# Power.net
KiCad netlist of a schematic drawn in Altium Designer
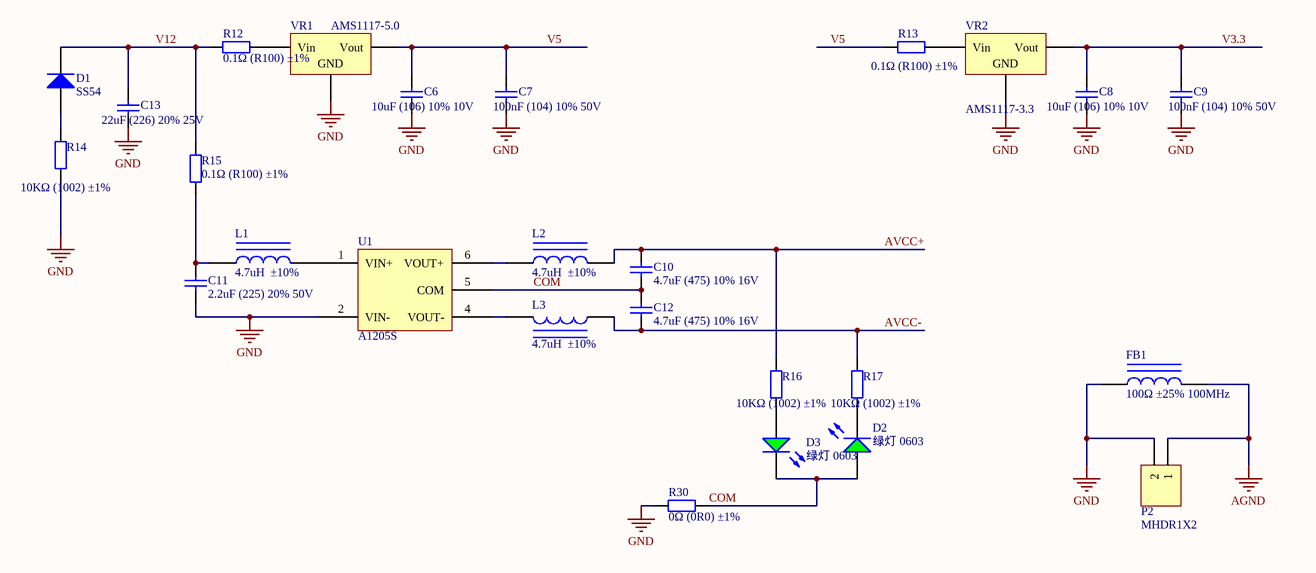
[diagram p0: Power.SchDoc]

(export (version "E")
  (design (tool "Eeschema 10.0.6"))
  (components
    (comp (ref "C6")
      (value "10uF (106) 10% 10V")
      (footprint "0603_C")
      (description "贴片电容")
      (libsource (lib "Miscellaneous Devices LC") (part "0603 10uF (106) 10% 10V"))
    )
    (comp (ref "C7")
      (value "100nF (104) 10% 50V")
      (footprint "0603_C")
      (description "贴片电容")
      (libsource (lib "Miscellaneous Devices LC") (part "0603 100nF (104) 10% 50V"))
    )
    (comp (ref "C8")
      (value "10uF (106) 10% 10V")
      (footprint "0603_C")
      (description "贴片电容")
      (libsource (lib "Miscellaneous Devices LC") (part "0603 10uF (106) 10% 10V"))
    )
    (comp (ref "C9")
      (value "100nF (104) 10% 50V")
      (footprint "0603_C")
      (description "贴片电容")
      (libsource (lib "Miscellaneous Devices LC") (part "0603 100nF (104) 10% 50V"))
    )
    (comp (ref "C10")
      (value "4.7uF (475) 10% 16V")
      (footprint "0603_C")
      (description "贴片电容")
      (libsource (lib "Miscellaneous Devices LC") (part "0603 4.7uF (475) 10% 16V"))
    )
    (comp (ref "C11")
      (value "2.2uF (225) 20% 50V")
      (footprint "0805_C")
      (description "贴片电容")
      (libsource (lib "Miscellaneous Devices LC") (part "0805 2.2uF (225) 20% 50V"))
    )
    (comp (ref "C12")
      (value "4.7uF (475) 10% 16V")
      (footprint "0603_C")
      (description "贴片电容")
      (libsource (lib "Miscellaneous Devices LC") (part "0603 4.7uF (475) 10% 16V"))
    )
    (comp (ref "C13")
      (value "22uF (226) 20% 25V")
      (footprint "0805_C")
      (description "贴片电容")
      (libsource (lib "Miscellaneous Devices LC") (part "0805 22uF (226) 20% 25V"))
    )
    (comp (ref "D1")
      (value "SS54")
      (footprint "SMA(DO-214AC)_S1")
      (description "二极管")
      (libsource (lib "Miscellaneous Devices LC") (part "SMA(DO-214AC) SS54"))
    )
    (comp (ref "D2")
      (value "绿灯 0603")
      (footprint "0603_LED_S1")
      (description "发光二极管")
      (libsource (lib "Miscellaneous Devices LC") (part "0603 绿灯"))
    )
    (comp (ref "D3")
      (value "绿灯 0603")
      (footprint "0603_LED_S1")
      (description "发光二极管")
      (libsource (lib "Miscellaneous Devices LC") (part "0603 绿灯"))
    )
    (comp (ref "FB1")
      (value "100Ω ±25% 100MHz")
      (footprint "0805_L")
      (description "贴片磁珠")
      (libsource (lib "Miscellaneous Devices LC") (part "0805 100Ω 25% 100MHz"))
    )
    (comp (ref "L1")
      (value "4.7uH  ±10%")
      (footprint "1206_L")
      (description "贴片电感")
      (libsource (lib "Miscellaneous Devices LC") (part "1206 4.7uH  10%"))
    )
    (comp (ref "L2")
      (value "4.7uH  ±10%")
      (footprint "1206_L")
      (description "贴片电感")
      (libsource (lib "Miscellaneous Devices LC") (part "1206 4.7uH  10%"))
    )
    (comp (ref "L3")
      (value "4.7uH  ±10%")
      (footprint "1206_L")
      (description "贴片电感")
      (libsource (lib "") (part "1206 4.7uH  10%_1"))
    )
    (comp (ref "P2")
      (value "MHDR1X2")
      (footprint "MHDR1X2")
      (description "Header, 2-Pin")
      (fields (field (name "PUBLISHER") "Altium Limited"))
      (libsource (lib "Miscellaneous Connectors") (part "MHDR1X2"))
    )
    (comp (ref "R12")
      (value "0.1Ω (R100) ±1%")
      (footprint "1206_R")
      (description "贴片电阻")
      (libsource (lib "Miscellaneous Devices LC") (part "1206 0.1Ω (R100) 1%"))
    )
    (comp (ref "R13")
      (value "0.1Ω (R100) ±1%")
      (footprint "1206_R")
      (description "贴片电阻")
      (libsource (lib "Miscellaneous Devices LC") (part "1206 0.1Ω (R100) 1%"))
    )
    (comp (ref "R14")
      (value "10KΩ (1002) ±1%")
      (footprint "0805_R")
      (description "贴片电阻")
      (libsource (lib "Miscellaneous Devices LC") (part "0805 10KΩ (1002) 1%"))
    )
    (comp (ref "R15")
      (value "0.1Ω (R100) ±1%")
      (footprint "1206_R")
      (description "贴片电阻")
      (libsource (lib "") (part "1206 0.1Ω (R100) 1%_1"))
    )
    (comp (ref "R16")
      (value "10KΩ (1002) ±1%")
      (footprint "0603_R")
      (description "贴片电阻")
      (libsource (lib "Miscellaneous Devices LC") (part "0603 10KΩ (1002) 1%"))
    )
    (comp (ref "R17")
      (value "10KΩ (1002) ±1%")
      (footprint "0603_R")
      (description "贴片电阻")
      (libsource (lib "Miscellaneous Devices LC") (part "0603 10KΩ (1002) 1%"))
    )
    (comp (ref "R30")
      (value "0Ω (0R0) ±1%")
      (footprint "1206_R")
      (description "贴片电阻")
      (libsource (lib "Miscellaneous Devices LC") (part "1206 0Ω (0R0) 1%"))
    )
    (comp (ref "U1") (value "A1205S") (footprint "A1205S") (libsource (lib "CHK-I") (part "A1205S")))
    (comp (ref "VR1")
      (value "AMS1117-5.0")
      (footprint "SOT-223")
      (description "低压差线性稳压(LDO)")
      (libsource (lib "Miscellaneous Devices LC") (part "SOT-223 AMS1117-5.0"))
    )
    (comp (ref "VR2")
      (value "AMS1117-3.3")
      (footprint "SOT-223")
      (description "低压差线性稳压(LDO)")
      (libsource (lib "Miscellaneous Devices LC") (part "SOT-223 AMS1117-3.3"))
    )
  )
  (nets
    (net (code "1") (name "/AVCC+") (class "Default")
      (node (ref "C10") (pin "2") (pinfunction "2_2") (pintype "passive"))
      (node (ref "L2") (pin "2") (pinfunction "2_2") (pintype "passive"))
      (node (ref "R16") (pin "2") (pinfunction "2_2") (pintype "passive"))
    )
    (net (code "2") (name "/AVCC-") (class "Default")
      (node (ref "C12") (pin "1") (pinfunction "1_1") (pintype "passive"))
      (node (ref "L3") (pin "2") (pinfunction "2_2") (pintype "passive"))
      (node (ref "R17") (pin "2") (pinfunction "2_2") (pintype "passive"))
    )
    (net (code "3") (name "/COM") (class "Default")
      (node (ref "C10") (pin "1") (pinfunction "1_1") (pintype "passive"))
      (node (ref "C12") (pin "2") (pinfunction "2_2") (pintype "passive"))
      (node (ref "D2") (pin "A") (pinfunction "A_A") (pintype "passive"))
      (node (ref "D3") (pin "K") (pinfunction "K_K") (pintype "passive"))
      (node (ref "R30") (pin "2") (pinfunction "2_2") (pintype "passive"))
      (node (ref "U1") (pin "5") (pinfunction "COM_5") (pintype "passive"))
    )
    (net (code "4") (name "/V3.3") (class "Default")
      (node (ref "C8") (pin "2") (pinfunction "2_2") (pintype "passive"))
      (node (ref "C9") (pin "2") (pinfunction "2_2") (pintype "passive"))
      (node (ref "VR2") (pin "2") (pinfunction "Vout_2") (pintype "passive"))
    )
    (net (code "5") (name "/V5") (class "Default")
      (node (ref "C6") (pin "2") (pinfunction "2_2") (pintype "passive"))
      (node (ref "C7") (pin "2") (pinfunction "2_2") (pintype "passive"))
      (node (ref "R13") (pin "1") (pinfunction "1_1") (pintype "passive"))
      (node (ref "VR1") (pin "2") (pinfunction "Vout_2") (pintype "passive"))
    )
    (net (code "6") (name "/V12") (class "Default")
      (node (ref "C13") (pin "2") (pinfunction "2_2") (pintype "passive"))
      (node (ref "D1") (pin "2") (pinfunction "K_2") (pintype "passive"))
      (node (ref "R12") (pin "1") (pinfunction "1_1") (pintype "passive"))
      (node (ref "R15") (pin "2") (pinfunction "2_2") (pintype "passive"))
    )
    (net (code "7") (name "AGND") (class "Default")
      (node (ref "FB1") (pin "2") (pinfunction "2_2") (pintype "passive"))
      (node (ref "P2") (pin "1") (pinfunction "1_1") (pintype "passive"))
    )
    (net (code "8") (name "GND") (class "Default")
      (node (ref "C11") (pin "1") (pinfunction "1_1") (pintype "passive"))
      (node (ref "C13") (pin "1") (pinfunction "1_1") (pintype "passive"))
      (node (ref "C6") (pin "1") (pinfunction "1_1") (pintype "passive"))
      (node (ref "C7") (pin "1") (pinfunction "1_1") (pintype "passive"))
      (node (ref "C8") (pin "1") (pinfunction "1_1") (pintype "passive"))
      (node (ref "C9") (pin "1") (pinfunction "1_1") (pintype "passive"))
      (node (ref "FB1") (pin "1") (pinfunction "1_1") (pintype "passive"))
      (node (ref "P2") (pin "2") (pinfunction "2_2") (pintype "passive"))
      (node (ref "R14") (pin "1") (pinfunction "1_1") (pintype "passive"))
      (node (ref "R30") (pin "1") (pinfunction "1_1") (pintype "passive"))
      (node (ref "U1") (pin "2") (pinfunction "VIN-_2") (pintype "passive"))
      (node (ref "VR1") (pin "1") (pinfunction "GND_1") (pintype "passive"))
      (node (ref "VR2") (pin "1") (pinfunction "GND_1") (pintype "passive"))
    )
    (net (code "9") (name "Net-(C11-Pad2)") (class "Default")
      (node (ref "C11") (pin "2") (pinfunction "2_2") (pintype "passive"))
      (node (ref "L1") (pin "1") (pinfunction "1_1") (pintype "passive"))
      (node (ref "R15") (pin "1") (pinfunction "1_1") (pintype "passive"))
    )
    (net (code "10") (name "Net-(D1-A)") (class "Default")
      (node (ref "D1") (pin "1") (pinfunction "A_1") (pintype "passive"))
      (node (ref "R14") (pin "2") (pinfunction "2_2") (pintype "passive"))
    )
    (net (code "11") (name "Net-(D2-PadK)") (class "Default")
      (node (ref "D2") (pin "K") (pinfunction "K_K") (pintype "passive"))
      (node (ref "R17") (pin "1") (pinfunction "1_1") (pintype "passive"))
    )
    (net (code "12") (name "Net-(D3-PadA)") (class "Default")
      (node (ref "D3") (pin "A") (pinfunction "A_A") (pintype "passive"))
      (node (ref "R16") (pin "1") (pinfunction "1_1") (pintype "passive"))
    )
    (net (code "13") (name "Net-(U1-VIN+)") (class "Default")
      (node (ref "L1") (pin "2") (pinfunction "2_2") (pintype "passive"))
      (node (ref "U1") (pin "1") (pinfunction "VIN+_1") (pintype "passive"))
    )
    (net (code "14") (name "Net-(U1-VOUT+)") (class "Default")
      (node (ref "L2") (pin "1") (pinfunction "1_1") (pintype "passive"))
      (node (ref "U1") (pin "6") (pinfunction "VOUT+_6") (pintype "passive"))
    )
    (net (code "15") (name "Net-(U1-VOUT-)") (class "Default")
      (node (ref "L3") (pin "1") (pinfunction "1_1") (pintype "passive"))
      (node (ref "U1") (pin "4") (pinfunction "VOUT-_4") (pintype "passive"))
    )
    (net (code "16") (name "Net-(VR1-Vin)") (class "Default")
      (node (ref "R12") (pin "2") (pinfunction "2_2") (pintype "passive"))
      (node (ref "VR1") (pin "3") (pinfunction "Vin_3") (pintype "passive"))
    )
    (net (code "17") (name "Net-(VR2-Vin)") (class "Default")
      (node (ref "R13") (pin "2") (pinfunction "2_2") (pintype "passive"))
      (node (ref "VR2") (pin "3") (pinfunction "Vin_3") (pintype "passive"))
    )
  )
)
